# 6_SWITCHING.net
KiCad netlist of a schematic drawn in Altium Designer
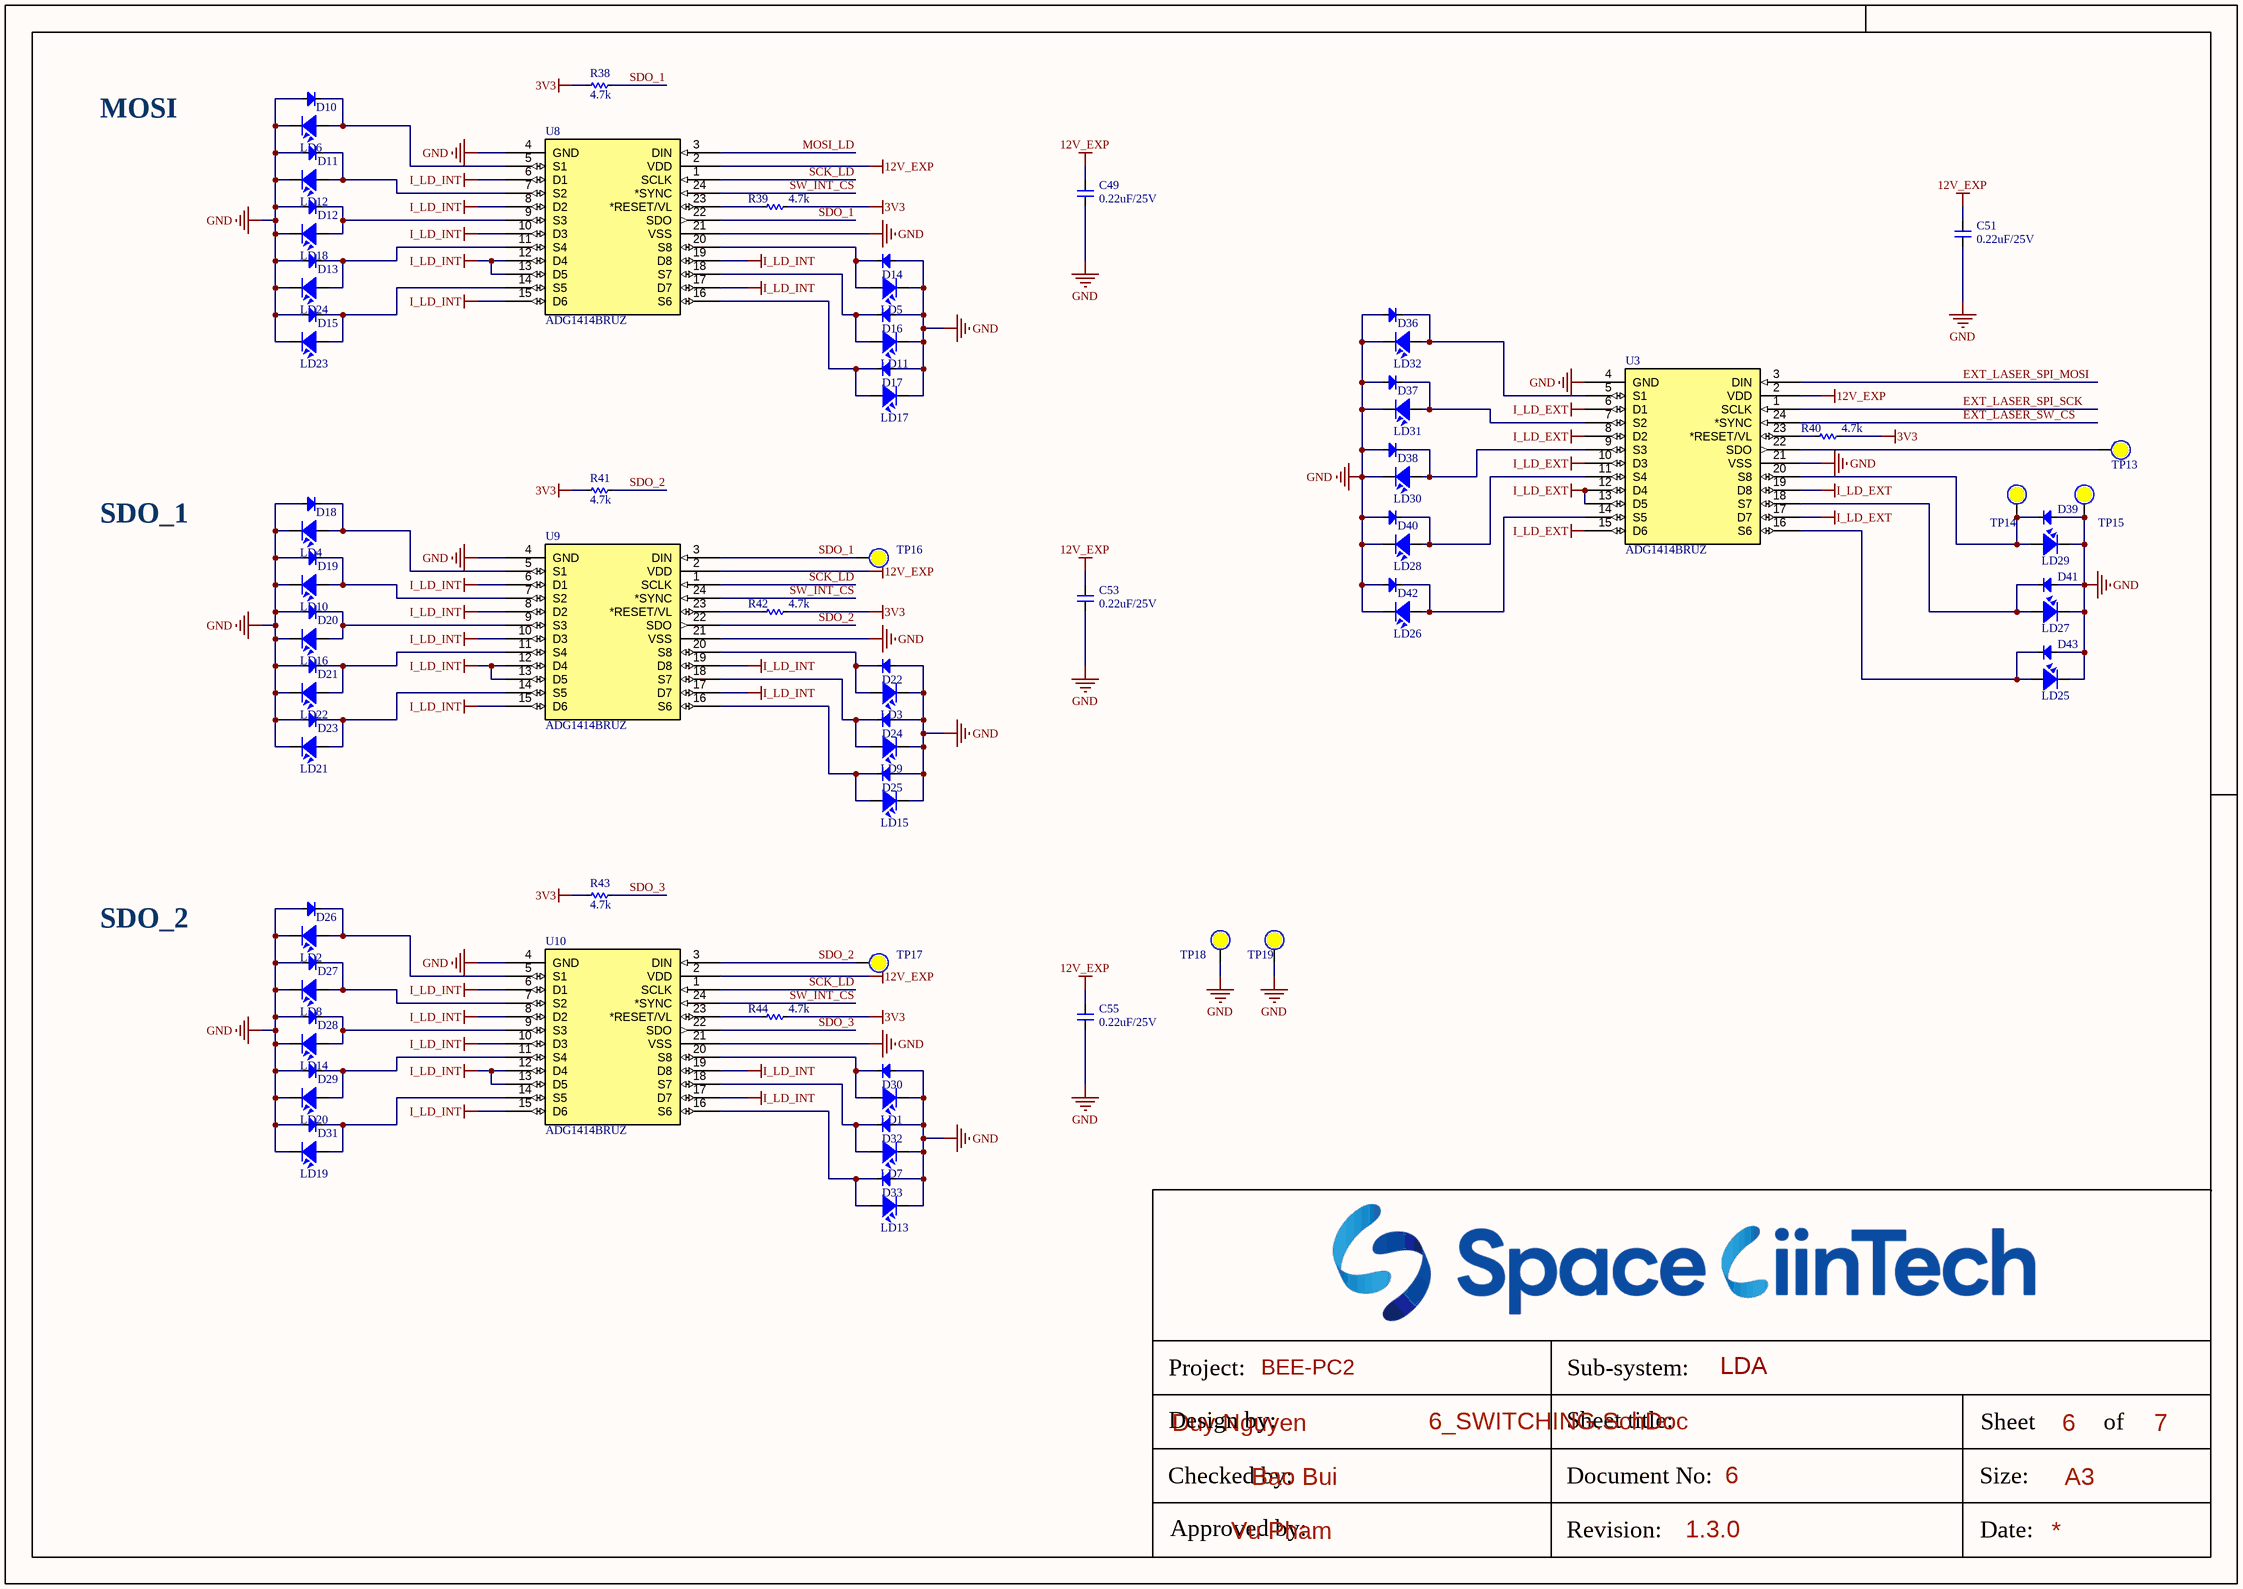
[diagram p0: 6_SWITCHING.SchDoc]

(export (version "E")
  (design (tool "Eeschema 10.0.6"))
  (components
    (comp (ref "C49")
      (value "0.22uF/25V")
      (footprint "CAP_C_1608X80")
      (description "CAP")
      (libsource (lib "LABLIB") (part "_CAP_C_2"))
    )
    (comp (ref "C51")
      (value "0.22uF/25V")
      (footprint "CAP_C_1608X80")
      (description "CAP")
      (libsource (lib "LABLIB") (part "_CAP_C_2"))
    )
    (comp (ref "C53")
      (value "0.22uF/25V")
      (footprint "CAP_C_1608X80")
      (description "CAP")
      (libsource (lib "LABLIB") (part "_CAP_C_2"))
    )
    (comp (ref "C55")
      (value "0.22uF/25V")
      (footprint "CAP_C_1608X80")
      (description "CAP")
      (libsource (lib "LABLIB") (part "_CAP_C_2"))
    )
    (comp (ref "D10")
      (value "1N4148W-TP")
      (footprint "SOD23")
      (fields (field (name "PUBLISHER") "Altium Limited"))
      (libsource (lib "LASER_LIB_SCHE") (part "Diode SMD"))
    )
    (comp (ref "D11")
      (value "1N4148W-TP")
      (footprint "SOD23")
      (fields (field (name "PUBLISHER") "Altium Limited"))
      (libsource (lib "LASER_LIB_SCHE") (part "Diode SMD"))
    )
    (comp (ref "D12")
      (value "1N4148W-TP")
      (footprint "SOD23")
      (fields (field (name "PUBLISHER") "Altium Limited"))
      (libsource (lib "LASER_LIB_SCHE") (part "Diode SMD"))
    )
    (comp (ref "D13")
      (value "1N4148W-TP")
      (footprint "SOD23")
      (fields (field (name "PUBLISHER") "Altium Limited"))
      (libsource (lib "LASER_LIB_SCHE") (part "Diode SMD"))
    )
    (comp (ref "D14")
      (value "1N4148W-TP")
      (footprint "SOD23")
      (fields (field (name "PUBLISHER") "Altium Limited"))
      (libsource (lib "LASER_LIB_SCHE") (part "Diode SMD"))
    )
    (comp (ref "D15")
      (value "1N4148W-TP")
      (footprint "SOD23")
      (fields (field (name "PUBLISHER") "Altium Limited"))
      (libsource (lib "LASER_LIB_SCHE") (part "Diode SMD"))
    )
    (comp (ref "D16")
      (value "1N4148W-TP")
      (footprint "SOD23")
      (fields (field (name "PUBLISHER") "Altium Limited"))
      (libsource (lib "LASER_LIB_SCHE") (part "Diode SMD"))
    )
    (comp (ref "D17")
      (value "1N4148W-TP")
      (footprint "SOD23")
      (fields (field (name "PUBLISHER") "Altium Limited"))
      (libsource (lib "LASER_LIB_SCHE") (part "Diode SMD"))
    )
    (comp (ref "D18")
      (value "1N4148W-TP")
      (footprint "SOD23")
      (fields (field (name "PUBLISHER") "Altium Limited"))
      (libsource (lib "LASER_LIB_SCHE") (part "Diode SMD"))
    )
    (comp (ref "D19")
      (value "1N4148W-TP")
      (footprint "SOD23")
      (fields (field (name "PUBLISHER") "Altium Limited"))
      (libsource (lib "LASER_LIB_SCHE") (part "Diode SMD"))
    )
    (comp (ref "D20")
      (value "1N4148W-TP")
      (footprint "SOD23")
      (fields (field (name "PUBLISHER") "Altium Limited"))
      (libsource (lib "LASER_LIB_SCHE") (part "Diode SMD"))
    )
    (comp (ref "D21")
      (value "1N4148W-TP")
      (footprint "SOD23")
      (fields (field (name "PUBLISHER") "Altium Limited"))
      (libsource (lib "LASER_LIB_SCHE") (part "Diode SMD"))
    )
    (comp (ref "D22")
      (value "1N4148W-TP")
      (footprint "SOD23")
      (fields (field (name "PUBLISHER") "Altium Limited"))
      (libsource (lib "LASER_LIB_SCHE") (part "Diode SMD"))
    )
    (comp (ref "D23")
      (value "1N4148W-TP")
      (footprint "SOD23")
      (fields (field (name "PUBLISHER") "Altium Limited"))
      (libsource (lib "LASER_LIB_SCHE") (part "Diode SMD"))
    )
    (comp (ref "D24")
      (value "1N4148W-TP")
      (footprint "SOD23")
      (fields (field (name "PUBLISHER") "Altium Limited"))
      (libsource (lib "LASER_LIB_SCHE") (part "Diode SMD"))
    )
    (comp (ref "D25")
      (value "1N4148W-TP")
      (footprint "SOD23")
      (fields (field (name "PUBLISHER") "Altium Limited"))
      (libsource (lib "LASER_LIB_SCHE") (part "Diode SMD"))
    )
    (comp (ref "D26")
      (value "1N4148W-TP")
      (footprint "SOD23")
      (fields (field (name "PUBLISHER") "Altium Limited"))
      (libsource (lib "LASER_LIB_SCHE") (part "Diode SMD"))
    )
    (comp (ref "D27")
      (value "1N4148W-TP")
      (footprint "SOD23")
      (fields (field (name "PUBLISHER") "Altium Limited"))
      (libsource (lib "LASER_LIB_SCHE") (part "Diode SMD"))
    )
    (comp (ref "D28")
      (value "1N4148W-TP")
      (footprint "SOD23")
      (fields (field (name "PUBLISHER") "Altium Limited"))
      (libsource (lib "LASER_LIB_SCHE") (part "Diode SMD"))
    )
    (comp (ref "D29")
      (value "1N4148W-TP")
      (footprint "SOD23")
      (fields (field (name "PUBLISHER") "Altium Limited"))
      (libsource (lib "LASER_LIB_SCHE") (part "Diode SMD"))
    )
    (comp (ref "D30")
      (value "1N4148W-TP")
      (footprint "SOD23")
      (fields (field (name "PUBLISHER") "Altium Limited"))
      (libsource (lib "LASER_LIB_SCHE") (part "Diode SMD"))
    )
    (comp (ref "D31")
      (value "1N4148W-TP")
      (footprint "SOD23")
      (fields (field (name "PUBLISHER") "Altium Limited"))
      (libsource (lib "LASER_LIB_SCHE") (part "Diode SMD"))
    )
    (comp (ref "D32")
      (value "1N4148W-TP")
      (footprint "SOD23")
      (fields (field (name "PUBLISHER") "Altium Limited"))
      (libsource (lib "LASER_LIB_SCHE") (part "Diode SMD"))
    )
    (comp (ref "D33")
      (value "1N4148W-TP")
      (footprint "SOD23")
      (fields (field (name "PUBLISHER") "Altium Limited"))
      (libsource (lib "LASER_LIB_SCHE") (part "Diode SMD"))
    )
    (comp (ref "D36")
      (value "1N4148W-TP")
      (footprint "SOD23")
      (fields (field (name "PUBLISHER") "Altium Limited"))
      (libsource (lib "LASER_LIB_SCHE") (part "Diode SMD"))
    )
    (comp (ref "D37")
      (value "1N4148W-TP")
      (footprint "SOD23")
      (fields (field (name "PUBLISHER") "Altium Limited"))
      (libsource (lib "LASER_LIB_SCHE") (part "Diode SMD"))
    )
    (comp (ref "D38")
      (value "1N4148W-TP")
      (footprint "SOD23")
      (fields (field (name "PUBLISHER") "Altium Limited"))
      (libsource (lib "LASER_LIB_SCHE") (part "Diode SMD"))
    )
    (comp (ref "D39")
      (value "1N4148W-TP")
      (footprint "SOD23")
      (fields (field (name "PUBLISHER") "Altium Limited"))
      (libsource (lib "LASER_LIB_SCHE") (part "Diode SMD"))
    )
    (comp (ref "D40")
      (value "1N4148W-TP")
      (footprint "SOD23")
      (fields (field (name "PUBLISHER") "Altium Limited"))
      (libsource (lib "LASER_LIB_SCHE") (part "Diode SMD"))
    )
    (comp (ref "D41")
      (value "1N4148W-TP")
      (footprint "SOD23")
      (fields (field (name "PUBLISHER") "Altium Limited"))
      (libsource (lib "LASER_LIB_SCHE") (part "Diode SMD"))
    )
    (comp (ref "D42")
      (value "1N4148W-TP")
      (footprint "SOD23")
      (fields (field (name "PUBLISHER") "Altium Limited"))
      (libsource (lib "LASER_LIB_SCHE") (part "Diode SMD"))
    )
    (comp (ref "D43")
      (value "1N4148W-TP")
      (footprint "SOD23")
      (fields (field (name "PUBLISHER") "Altium Limited"))
      (libsource (lib "LASER_LIB_SCHE") (part "Diode SMD"))
    )
    (comp (ref "LD1")
      (value "LaserDiode")
      (footprint "OPV302")
      (description "OPV302")
      (libsource (lib "LASER_LIB_SCHE") (part "LD"))
    )
    (comp (ref "LD2")
      (value "LaserDiode")
      (footprint "OPV302")
      (description "OPV302")
      (libsource (lib "LASER_LIB_SCHE") (part "LD"))
    )
    (comp (ref "LD3")
      (value "LaserDiode")
      (footprint "OPV302")
      (description "OPV302")
      (libsource (lib "LASER_LIB_SCHE") (part "LD"))
    )
    (comp (ref "LD4")
      (value "LaserDiode")
      (footprint "OPV302")
      (description "OPV302")
      (libsource (lib "LASER_LIB_SCHE") (part "LD"))
    )
    (comp (ref "LD5")
      (value "LaserDiode")
      (footprint "OPV302")
      (description "OPV302")
      (libsource (lib "LASER_LIB_SCHE") (part "LD"))
    )
    (comp (ref "LD6")
      (value "LaserDiode")
      (footprint "OPV302")
      (description "OPV302")
      (libsource (lib "LASER_LIB_SCHE") (part "LD"))
    )
    (comp (ref "LD7")
      (value "LaserDiode")
      (footprint "OPV302")
      (description "OPV302")
      (libsource (lib "LASER_LIB_SCHE") (part "LD"))
    )
    (comp (ref "LD8")
      (value "LaserDiode")
      (footprint "OPV302")
      (description "OPV302")
      (libsource (lib "LASER_LIB_SCHE") (part "LD"))
    )
    (comp (ref "LD9")
      (value "LaserDiode")
      (footprint "OPV302")
      (description "OPV302")
      (libsource (lib "LASER_LIB_SCHE") (part "LD"))
    )
    (comp (ref "LD10")
      (value "LaserDiode")
      (footprint "OPV302")
      (description "OPV302")
      (libsource (lib "LASER_LIB_SCHE") (part "LD"))
    )
    (comp (ref "LD11")
      (value "LaserDiode")
      (footprint "OPV302")
      (description "OPV302")
      (libsource (lib "LASER_LIB_SCHE") (part "LD"))
    )
    (comp (ref "LD12")
      (value "LaserDiode")
      (footprint "OPV302")
      (description "OPV302")
      (libsource (lib "LASER_LIB_SCHE") (part "LD"))
    )
    (comp (ref "LD13")
      (value "LaserDiode")
      (footprint "OPV302")
      (description "OPV302")
      (libsource (lib "LASER_LIB_SCHE") (part "LD"))
    )
    (comp (ref "LD14")
      (value "LaserDiode")
      (footprint "OPV302")
      (description "OPV302")
      (libsource (lib "LASER_LIB_SCHE") (part "LD"))
    )
    (comp (ref "LD15")
      (value "LaserDiode")
      (footprint "OPV302")
      (description "OPV302")
      (libsource (lib "LASER_LIB_SCHE") (part "LD"))
    )
    (comp (ref "LD16")
      (value "LaserDiode")
      (footprint "OPV302")
      (description "OPV302")
      (libsource (lib "LASER_LIB_SCHE") (part "LD"))
    )
    (comp (ref "LD17")
      (value "LaserDiode")
      (footprint "OPV302")
      (description "OPV302")
      (libsource (lib "LASER_LIB_SCHE") (part "LD"))
    )
    (comp (ref "LD18")
      (value "LaserDiode")
      (footprint "OPV302")
      (description "OPV302")
      (libsource (lib "LASER_LIB_SCHE") (part "LD"))
    )
    (comp (ref "LD19")
      (value "LaserDiode")
      (footprint "OPV302")
      (description "OPV302")
      (libsource (lib "LASER_LIB_SCHE") (part "LD"))
    )
    (comp (ref "LD20")
      (value "LaserDiode")
      (footprint "OPV302")
      (description "OPV302")
      (libsource (lib "LASER_LIB_SCHE") (part "LD"))
    )
    (comp (ref "LD21")
      (value "LaserDiode")
      (footprint "OPV302")
      (description "OPV302")
      (libsource (lib "LASER_LIB_SCHE") (part "LD"))
    )
    (comp (ref "LD22")
      (value "LaserDiode")
      (footprint "OPV302")
      (description "OPV302")
      (libsource (lib "LASER_LIB_SCHE") (part "LD"))
    )
    (comp (ref "LD23")
      (value "LaserDiode")
      (footprint "OPV302")
      (description "OPV302")
      (libsource (lib "LASER_LIB_SCHE") (part "LD"))
    )
    (comp (ref "LD24")
      (value "LaserDiode")
      (footprint "OPV302")
      (description "OPV302")
      (libsource (lib "LASER_LIB_SCHE") (part "LD"))
    )
    (comp (ref "LD25")
      (value "LaserDiode")
      (footprint "RLD65NZX1")
      (description "RLD65NZX1")
      (libsource (lib "LASER_LIB_SCHE") (part "LD_RLD65NZX1"))
    )
    (comp (ref "LD26")
      (value "LaserDiode")
      (footprint "RLD65NZX1")
      (description "RLD65NZX1")
      (libsource (lib "LASER_LIB_SCHE") (part "LD_RLD65NZX1"))
    )
    (comp (ref "LD27")
      (value "LaserDiode")
      (footprint "RLD65NZX1")
      (description "RLD65NZX1")
      (libsource (lib "LASER_LIB_SCHE") (part "LD_RLD65NZX1"))
    )
    (comp (ref "LD28")
      (value "LaserDiode")
      (footprint "RLD65NZX1")
      (description "RLD65NZX1")
      (libsource (lib "LASER_LIB_SCHE") (part "LD_RLD65NZX1"))
    )
    (comp (ref "LD29")
      (value "LaserDiode")
      (footprint "RLD65NZX1")
      (description "RLD65NZX1")
      (libsource (lib "LASER_LIB_SCHE") (part "LD_RLD65NZX1"))
    )
    (comp (ref "LD30")
      (value "LaserDiode")
      (footprint "RLD65NZX1")
      (description "RLD65NZX1")
      (libsource (lib "LASER_LIB_SCHE") (part "LD_RLD65NZX1"))
    )
    (comp (ref "LD31")
      (value "LaserDiode")
      (footprint "RLD65NZX1")
      (description "RLD65NZX1")
      (libsource (lib "LASER_LIB_SCHE") (part "LD_RLD65NZX1"))
    )
    (comp (ref "LD32")
      (value "LaserDiode")
      (footprint "RLD65NZX1")
      (description "RLD65NZX1")
      (libsource (lib "LASER_LIB_SCHE") (part "LD_RLD65NZX1"))
    )
    (comp (ref "R38")
      (value "4.7k")
      (footprint "RES_C_1608X60")
      (description "RES")
      (libsource (lib "LABLIB") (part "_RES_B_2"))
    )
    (comp (ref "R39")
      (value "4.7k")
      (footprint "RES_C_1608X60")
      (description "RES")
      (libsource (lib "LABLIB") (part "_RES_B_2"))
    )
    (comp (ref "R40")
      (value "4.7k")
      (footprint "RES_C_1608X60")
      (description "RES")
      (libsource (lib "LABLIB") (part "_RES_B_2"))
    )
    (comp (ref "R41")
      (value "4.7k")
      (footprint "RES_C_1608X60")
      (description "RES")
      (libsource (lib "LABLIB") (part "_RES_B_2"))
    )
    (comp (ref "R42")
      (value "4.7k")
      (footprint "RES_C_1608X60")
      (description "RES")
      (libsource (lib "LABLIB") (part "_RES_B_2"))
    )
    (comp (ref "R43")
      (value "4.7k")
      (footprint "RES_C_1608X60")
      (description "RES")
      (libsource (lib "LABLIB") (part "_RES_B_2"))
    )
    (comp (ref "R44")
      (value "4.7k")
      (footprint "RES_C_1608X60")
      (description "RES")
      (libsource (lib "LABLIB") (part "_RES_B_2"))
    )
    (comp (ref "TP13")
      (value "~")
      (footprint "Testpoint_80")
      (description "Test Point")
      (libsource (lib "LASER_LIB_SCHE") (part "Test Point"))
    )
    (comp (ref "TP14")
      (value "~")
      (footprint "Testpoint_80")
      (description "Test Point")
      (libsource (lib "") (part "Test Point_1"))
    )
    (comp (ref "TP15")
      (value "~")
      (footprint "Testpoint_80")
      (description "Test Point")
      (libsource (lib "") (part "Test Point_1"))
    )
    (comp (ref "TP16")
      (value "~")
      (footprint "Testpoint_80")
      (description "Test Point")
      (libsource (lib "LASER_LIB_SCHE") (part "Test Point"))
    )
    (comp (ref "TP17")
      (value "~")
      (footprint "Testpoint_80")
      (description "Test Point")
      (libsource (lib "LASER_LIB_SCHE") (part "Test Point"))
    )
    (comp (ref "TP18")
      (value "~")
      (footprint "Testpoint_80")
      (description "Test Point")
      (libsource (lib "") (part "Test Point_1"))
    )
    (comp (ref "TP19")
      (value "~")
      (footprint "Testpoint_80")
      (description "Test Point")
      (libsource (lib "") (part "Test Point_1"))
    )
    (comp (ref "U3")
      (value "ADG1414BRUZ")
      (footprint "TSSOP24")
      (libsource (lib "LASER_LIB_SCHE") (part "ADG1414BRUZ"))
    )
    (comp (ref "U8")
      (value "ADG1414BRUZ")
      (footprint "TSSOP24")
      (libsource (lib "LASER_LIB_SCHE") (part "ADG1414BRUZ"))
    )
    (comp (ref "U9")
      (value "ADG1414BRUZ")
      (footprint "TSSOP24")
      (libsource (lib "LASER_LIB_SCHE") (part "ADG1414BRUZ"))
    )
    (comp (ref "U10")
      (value "ADG1414BRUZ")
      (footprint "TSSOP24")
      (libsource (lib "LASER_LIB_SCHE") (part "ADG1414BRUZ"))
    )
  )
  (nets
    (net (code "1") (name "/EXT_LASER_SPI_MOSI") (class "Default")
      (node (ref "U3") (pin "3") (pinfunction "DIN_3") (pintype "input"))
    )
    (net (code "2") (name "/EXT_LASER_SPI_SCK") (class "Default")
      (node (ref "U3") (pin "1") (pinfunction "SCLK_1") (pintype "input"))
    )
    (net (code "3") (name "/EXT_LASER_SW_CS") (class "Default")
      (node (ref "U3") (pin "24") (pinfunction "*SYNC_24") (pintype "input"))
    )
    (net (code "4") (name "/MOSI_LD") (class "Default")
      (node (ref "U8") (pin "3") (pinfunction "DIN_3") (pintype "input"))
    )
    (net (code "5") (name "/SCK_LD") (class "Default")
      (node (ref "U10") (pin "1") (pinfunction "SCLK_1") (pintype "input"))
      (node (ref "U8") (pin "1") (pinfunction "SCLK_1") (pintype "input"))
      (node (ref "U9") (pin "1") (pinfunction "SCLK_1") (pintype "input"))
    )
    (net (code "6") (name "/SDO_1") (class "Default")
      (node (ref "R38") (pin "2") (pinfunction "2_2") (pintype "passive"))
      (node (ref "TP16") (pin "1") (pinfunction "1_1") (pintype "passive"))
      (node (ref "U8") (pin "22") (pinfunction "SDO_22") (pintype "output"))
      (node (ref "U9") (pin "3") (pinfunction "DIN_3") (pintype "input"))
    )
    (net (code "7") (name "/SDO_2") (class "Default")
      (node (ref "R41") (pin "2") (pinfunction "2_2") (pintype "passive"))
      (node (ref "TP17") (pin "1") (pinfunction "1_1") (pintype "passive"))
      (node (ref "U10") (pin "3") (pinfunction "DIN_3") (pintype "input"))
      (node (ref "U9") (pin "22") (pinfunction "SDO_22") (pintype "output"))
    )
    (net (code "8") (name "/SDO_3") (class "Default")
      (node (ref "R43") (pin "2") (pinfunction "2_2") (pintype "passive"))
      (node (ref "U10") (pin "22") (pinfunction "SDO_22") (pintype "output"))
    )
    (net (code "9") (name "/SW_INT_CS") (class "Default")
      (node (ref "U10") (pin "24") (pinfunction "*SYNC_24") (pintype "input"))
      (node (ref "U8") (pin "24") (pinfunction "*SYNC_24") (pintype "input"))
      (node (ref "U9") (pin "24") (pinfunction "*SYNC_24") (pintype "input"))
    )
    (net (code "10") (name "3V3") (class "Default")
      (node (ref "R38") (pin "1") (pinfunction "1_1") (pintype "passive"))
      (node (ref "R39") (pin "2") (pinfunction "2_2") (pintype "passive"))
      (node (ref "R40") (pin "2") (pinfunction "2_2") (pintype "passive"))
      (node (ref "R41") (pin "1") (pinfunction "1_1") (pintype "passive"))
      (node (ref "R42") (pin "2") (pinfunction "2_2") (pintype "passive"))
      (node (ref "R43") (pin "1") (pinfunction "1_1") (pintype "passive"))
      (node (ref "R44") (pin "2") (pinfunction "2_2") (pintype "passive"))
    )
    (net (code "11") (name "12V_EXP") (class "Default")
      (node (ref "C49") (pin "2") (pinfunction "2_2") (pintype "passive"))
      (node (ref "C51") (pin "2") (pinfunction "2_2") (pintype "passive"))
      (node (ref "C53") (pin "2") (pinfunction "2_2") (pintype "passive"))
      (node (ref "C55") (pin "2") (pinfunction "2_2") (pintype "passive"))
      (node (ref "U10") (pin "2") (pinfunction "VDD_2") (pintype "power_in"))
      (node (ref "U3") (pin "2") (pinfunction "VDD_2") (pintype "power_in"))
      (node (ref "U8") (pin "2") (pinfunction "VDD_2") (pintype "power_in"))
      (node (ref "U9") (pin "2") (pinfunction "VDD_2") (pintype "power_in"))
    )
    (net (code "12") (name "GND") (class "Default")
      (node (ref "C49") (pin "1") (pinfunction "1_1") (pintype "passive"))
      (node (ref "C51") (pin "1") (pinfunction "1_1") (pintype "passive"))
      (node (ref "C53") (pin "1") (pinfunction "1_1") (pintype "passive"))
      (node (ref "C55") (pin "1") (pinfunction "1_1") (pintype "passive"))
      (node (ref "D10") (pin "1") (pinfunction "A_1") (pintype "passive"))
      (node (ref "D11") (pin "1") (pinfunction "A_1") (pintype "passive"))
      (node (ref "D12") (pin "1") (pinfunction "A_1") (pintype "passive"))
      (node (ref "D13") (pin "1") (pinfunction "A_1") (pintype "passive"))
      (node (ref "D14") (pin "1") (pinfunction "A_1") (pintype "passive"))
      (node (ref "D15") (pin "1") (pinfunction "A_1") (pintype "passive"))
      (node (ref "D16") (pin "1") (pinfunction "A_1") (pintype "passive"))
      (node (ref "D17") (pin "1") (pinfunction "A_1") (pintype "passive"))
      (node (ref "D18") (pin "1") (pinfunction "A_1") (pintype "passive"))
      (node (ref "D19") (pin "1") (pinfunction "A_1") (pintype "passive"))
      (node (ref "D20") (pin "1") (pinfunction "A_1") (pintype "passive"))
      (node (ref "D21") (pin "1") (pinfunction "A_1") (pintype "passive"))
      (node (ref "D22") (pin "1") (pinfunction "A_1") (pintype "passive"))
      (node (ref "D23") (pin "1") (pinfunction "A_1") (pintype "passive"))
      (node (ref "D24") (pin "1") (pinfunction "A_1") (pintype "passive"))
      (node (ref "D25") (pin "1") (pinfunction "A_1") (pintype "passive"))
      (node (ref "D26") (pin "1") (pinfunction "A_1") (pintype "passive"))
      (node (ref "D27") (pin "1") (pinfunction "A_1") (pintype "passive"))
      (node (ref "D28") (pin "1") (pinfunction "A_1") (pintype "passive"))
      (node (ref "D29") (pin "1") (pinfunction "A_1") (pintype "passive"))
      (node (ref "D30") (pin "1") (pinfunction "A_1") (pintype "passive"))
      (node (ref "D31") (pin "1") (pinfunction "A_1") (pintype "passive"))
      (node (ref "D32") (pin "1") (pinfunction "A_1") (pintype "passive"))
      (node (ref "D33") (pin "1") (pinfunction "A_1") (pintype "passive"))
      (node (ref "D36") (pin "1") (pinfunction "A_1") (pintype "passive"))
      (node (ref "D37") (pin "1") (pinfunction "A_1") (pintype "passive"))
      (node (ref "D38") (pin "1") (pinfunction "A_1") (pintype "passive"))
      (node (ref "D39") (pin "1") (pinfunction "A_1") (pintype "passive"))
      (node (ref "D40") (pin "1") (pinfunction "A_1") (pintype "passive"))
      (node (ref "D41") (pin "1") (pinfunction "A_1") (pintype "passive"))
      (node (ref "D42") (pin "1") (pinfunction "A_1") (pintype "passive"))
      (node (ref "D43") (pin "1") (pinfunction "A_1") (pintype "passive"))
      (node (ref "LD1") (pin "2") (pinfunction "2_2") (pintype "passive"))
      (node (ref "LD10") (pin "2") (pinfunction "2_2") (pintype "passive"))
      (node (ref "LD11") (pin "2") (pinfunction "2_2") (pintype "passive"))
      (node (ref "LD12") (pin "2") (pinfunction "2_2") (pintype "passive"))
      (node (ref "LD13") (pin "2") (pinfunction "2_2") (pintype "passive"))
      (node (ref "LD14") (pin "2") (pinfunction "2_2") (pintype "passive"))
      (node (ref "LD15") (pin "2") (pinfunction "2_2") (pintype "passive"))
      (node (ref "LD16") (pin "2") (pinfunction "2_2") (pintype "passive"))
      (node (ref "LD17") (pin "2") (pinfunction "2_2") (pintype "passive"))
      (node (ref "LD18") (pin "2") (pinfunction "2_2") (pintype "passive"))
      (node (ref "LD19") (pin "2") (pinfunction "2_2") (pintype "passive"))
      (node (ref "LD2") (pin "2") (pinfunction "2_2") (pintype "passive"))
      (node (ref "LD20") (pin "2") (pinfunction "2_2") (pintype "passive"))
      (node (ref "LD21") (pin "2") (pinfunction "2_2") (pintype "passive"))
      (node (ref "LD22") (pin "2") (pinfunction "2_2") (pintype "passive"))
      (node (ref "LD23") (pin "2") (pinfunction "2_2") (pintype "passive"))
      (node (ref "LD24") (pin "2") (pinfunction "2_2") (pintype "passive"))
      (node (ref "LD25") (pin "1") (pinfunction "1_1") (pintype "passive"))
      (node (ref "LD26") (pin "1") (pinfunction "1_1") (pintype "passive"))
      (node (ref "LD27") (pin "1") (pinfunction "1_1") (pintype "passive"))
      (node (ref "LD28") (pin "1") (pinfunction "1_1") (pintype "passive"))
      (node (ref "LD29") (pin "1") (pinfunction "1_1") (pintype "passive"))
      (node (ref "LD3") (pin "2") (pinfunction "2_2") (pintype "passive"))
      (node (ref "LD30") (pin "1") (pinfunction "1_1") (pintype "passive"))
      (node (ref "LD31") (pin "1") (pinfunction "1_1") (pintype "passive"))
      (node (ref "LD32") (pin "1") (pinfunction "1_1") (pintype "passive"))
      (node (ref "LD4") (pin "2") (pinfunction "2_2") (pintype "passive"))
      (node (ref "LD5") (pin "2") (pinfunction "2_2") (pintype "passive"))
      (node (ref "LD6") (pin "2") (pinfunction "2_2") (pintype "passive"))
      (node (ref "LD7") (pin "2") (pinfunction "2_2") (pintype "passive"))
      (node (ref "LD8") (pin "2") (pinfunction "2_2") (pintype "passive"))
      (node (ref "LD9") (pin "2") (pinfunction "2_2") (pintype "passive"))
      (node (ref "TP15") (pin "1") (pinfunction "1_1") (pintype "passive"))
      (node (ref "TP18") (pin "1") (pinfunction "1_1") (pintype "passive"))
      (node (ref "TP19") (pin "1") (pinfunction "1_1") (pintype "passive"))
      (node (ref "U10") (pin "21") (pinfunction "VSS_21") (pintype "power_in"))
      (node (ref "U10") (pin "4") (pinfunction "GND_4") (pintype "power_in"))
      (node (ref "U3") (pin "21") (pinfunction "VSS_21") (pintype "power_in"))
      (node (ref "U3") (pin "4") (pinfunction "GND_4") (pintype "power_in"))
      (node (ref "U8") (pin "21") (pinfunction "VSS_21") (pintype "power_in"))
      (node (ref "U8") (pin "4") (pinfunction "GND_4") (pintype "power_in"))
      (node (ref "U9") (pin "21") (pinfunction "VSS_21") (pintype "power_in"))
      (node (ref "U9") (pin "4") (pinfunction "GND_4") (pintype "power_in"))
    )
    (net (code "13") (name "I_LD_EXT") (class "Default")
      (node (ref "U3") (pin "10") (pinfunction "D3_10") (pintype "bidirectional"))
      (node (ref "U3") (pin "12") (pinfunction "D4_12") (pintype "bidirectional"))
      (node (ref "U3") (pin "13") (pinfunction "D5_13") (pintype "bidirectional"))
      (node (ref "U3") (pin "15") (pinfunction "D6_15") (pintype "bidirectional"))
      (node (ref "U3") (pin "17") (pinfunction "D7_17") (pintype "bidirectional"))
      (node (ref "U3") (pin "19") (pinfunction "D8_19") (pintype "bidirectional"))
      (node (ref "U3") (pin "6") (pinfunction "D1_6") (pintype "bidirectional"))
      (node (ref "U3") (pin "8") (pinfunction "D2_8") (pintype "bidirectional"))
    )
    (net (code "14") (name "I_LD_INT") (class "Default")
      (node (ref "U10") (pin "10") (pinfunction "D3_10") (pintype "bidirectional"))
      (node (ref "U10") (pin "12") (pinfunction "D4_12") (pintype "bidirectional"))
      (node (ref "U10") (pin "13") (pinfunction "D5_13") (pintype "bidirectional"))
      (node (ref "U10") (pin "15") (pinfunction "D6_15") (pintype "bidirectional"))
      (node (ref "U10") (pin "17") (pinfunction "D7_17") (pintype "bidirectional"))
      (node (ref "U10") (pin "19") (pinfunction "D8_19") (pintype "bidirectional"))
      (node (ref "U10") (pin "6") (pinfunction "D1_6") (pintype "bidirectional"))
      (node (ref "U10") (pin "8") (pinfunction "D2_8") (pintype "bidirectional"))
      (node (ref "U8") (pin "10") (pinfunction "D3_10") (pintype "bidirectional"))
      (node (ref "U8") (pin "12") (pinfunction "D4_12") (pintype "bidirectional"))
      (node (ref "U8") (pin "13") (pinfunction "D5_13") (pintype "bidirectional"))
      (node (ref "U8") (pin "15") (pinfunction "D6_15") (pintype "bidirectional"))
      (node (ref "U8") (pin "17") (pinfunction "D7_17") (pintype "bidirectional"))
      (node (ref "U8") (pin "19") (pinfunction "D8_19") (pintype "bidirectional"))
      (node (ref "U8") (pin "6") (pinfunction "D1_6") (pintype "bidirectional"))
      (node (ref "U8") (pin "8") (pinfunction "D2_8") (pintype "bidirectional"))
      (node (ref "U9") (pin "10") (pinfunction "D3_10") (pintype "bidirectional"))
      (node (ref "U9") (pin "12") (pinfunction "D4_12") (pintype "bidirectional"))
      (node (ref "U9") (pin "13") (pinfunction "D5_13") (pintype "bidirectional"))
      (node (ref "U9") (pin "15") (pinfunction "D6_15") (pintype "bidirectional"))
      (node (ref "U9") (pin "17") (pinfunction "D7_17") (pintype "bidirectional"))
      (node (ref "U9") (pin "19") (pinfunction "D8_19") (pintype "bidirectional"))
      (node (ref "U9") (pin "6") (pinfunction "D1_6") (pintype "bidirectional"))
      (node (ref "U9") (pin "8") (pinfunction "D2_8") (pintype "bidirectional"))
    )
    (net (code "15") (name "Net-(D10-K)") (class "Default")
      (node (ref "D10") (pin "2") (pinfunction "K_2") (pintype "passive"))
      (node (ref "LD6") (pin "1") (pinfunction "1_1") (pintype "passive"))
      (node (ref "U8") (pin "5") (pinfunction "S1_5") (pintype "bidirectional"))
    )
    (net (code "16") (name "Net-(D11-K)") (class "Default")
      (node (ref "D11") (pin "2") (pinfunction "K_2") (pintype "passive"))
      (node (ref "LD12") (pin "1") (pinfunction "1_1") (pintype "passive"))
      (node (ref "U8") (pin "7") (pinfunction "S2_7") (pintype "bidirectional"))
    )
    (net (code "17") (name "Net-(D12-K)") (class "Default")
      (node (ref "D12") (pin "2") (pinfunction "K_2") (pintype "passive"))
      (node (ref "LD18") (pin "1") (pinfunction "1_1") (pintype "passive"))
      (node (ref "U8") (pin "9") (pinfunction "S3_9") (pintype "bidirectional"))
    )
    (net (code "18") (name "Net-(D13-K)") (class "Default")
      (node (ref "D13") (pin "2") (pinfunction "K_2") (pintype "passive"))
      (node (ref "LD24") (pin "1") (pinfunction "1_1") (pintype "passive"))
      (node (ref "U8") (pin "11") (pinfunction "S4_11") (pintype "bidirectional"))
    )
    (net (code "19") (name "Net-(D14-K)") (class "Default")
      (node (ref "D14") (pin "2") (pinfunction "K_2") (pintype "passive"))
      (node (ref "LD5") (pin "1") (pinfunction "1_1") (pintype "passive"))
      (node (ref "U8") (pin "20") (pinfunction "S8_20") (pintype "bidirectional"))
    )
    (net (code "20") (name "Net-(D15-K)") (class "Default")
      (node (ref "D15") (pin "2") (pinfunction "K_2") (pintype "passive"))
      (node (ref "LD23") (pin "1") (pinfunction "1_1") (pintype "passive"))
      (node (ref "U8") (pin "14") (pinfunction "S5_14") (pintype "bidirectional"))
    )
    (net (code "21") (name "Net-(D16-K)") (class "Default")
      (node (ref "D16") (pin "2") (pinfunction "K_2") (pintype "passive"))
      (node (ref "LD11") (pin "1") (pinfunction "1_1") (pintype "passive"))
      (node (ref "U8") (pin "18") (pinfunction "S7_18") (pintype "bidirectional"))
    )
    (net (code "22") (name "Net-(D17-K)") (class "Default")
      (node (ref "D17") (pin "2") (pinfunction "K_2") (pintype "passive"))
      (node (ref "LD17") (pin "1") (pinfunction "1_1") (pintype "passive"))
      (node (ref "U8") (pin "16") (pinfunction "S6_16") (pintype "bidirectional"))
    )
    (net (code "23") (name "Net-(D18-K)") (class "Default")
      (node (ref "D18") (pin "2") (pinfunction "K_2") (pintype "passive"))
      (node (ref "LD4") (pin "1") (pinfunction "1_1") (pintype "passive"))
      (node (ref "U9") (pin "5") (pinfunction "S1_5") (pintype "bidirectional"))
    )
    (net (code "24") (name "Net-(D19-K)") (class "Default")
      (node (ref "D19") (pin "2") (pinfunction "K_2") (pintype "passive"))
      (node (ref "LD10") (pin "1") (pinfunction "1_1") (pintype "passive"))
      (node (ref "U9") (pin "7") (pinfunction "S2_7") (pintype "bidirectional"))
    )
    (net (code "25") (name "Net-(D20-K)") (class "Default")
      (node (ref "D20") (pin "2") (pinfunction "K_2") (pintype "passive"))
      (node (ref "LD16") (pin "1") (pinfunction "1_1") (pintype "passive"))
      (node (ref "U9") (pin "9") (pinfunction "S3_9") (pintype "bidirectional"))
    )
    (net (code "26") (name "Net-(D21-K)") (class "Default")
      (node (ref "D21") (pin "2") (pinfunction "K_2") (pintype "passive"))
      (node (ref "LD22") (pin "1") (pinfunction "1_1") (pintype "passive"))
      (node (ref "U9") (pin "11") (pinfunction "S4_11") (pintype "bidirectional"))
    )
    (net (code "27") (name "Net-(D22-K)") (class "Default")
      (node (ref "D22") (pin "2") (pinfunction "K_2") (pintype "passive"))
      (node (ref "LD3") (pin "1") (pinfunction "1_1") (pintype "passive"))
      (node (ref "U9") (pin "20") (pinfunction "S8_20") (pintype "bidirectional"))
    )
    (net (code "28") (name "Net-(D23-K)") (class "Default")
      (node (ref "D23") (pin "2") (pinfunction "K_2") (pintype "passive"))
      (node (ref "LD21") (pin "1") (pinfunction "1_1") (pintype "passive"))
      (node (ref "U9") (pin "14") (pinfunction "S5_14") (pintype "bidirectional"))
    )
    (net (code "29") (name "Net-(D24-K)") (class "Default")
      (node (ref "D24") (pin "2") (pinfunction "K_2") (pintype "passive"))
      (node (ref "LD9") (pin "1") (pinfunction "1_1") (pintype "passive"))
      (node (ref "U9") (pin "18") (pinfunction "S7_18") (pintype "bidirectional"))
    )
    (net (code "30") (name "Net-(D25-K)") (class "Default")
      (node (ref "D25") (pin "2") (pinfunction "K_2") (pintype "passive"))
      (node (ref "LD15") (pin "1") (pinfunction "1_1") (pintype "passive"))
      (node (ref "U9") (pin "16") (pinfunction "S6_16") (pintype "bidirectional"))
    )
    (net (code "31") (name "Net-(D26-K)") (class "Default")
      (node (ref "D26") (pin "2") (pinfunction "K_2") (pintype "passive"))
      (node (ref "LD2") (pin "1") (pinfunction "1_1") (pintype "passive"))
      (node (ref "U10") (pin "5") (pinfunction "S1_5") (pintype "bidirectional"))
    )
    (net (code "32") (name "Net-(D27-K)") (class "Default")
      (node (ref "D27") (pin "2") (pinfunction "K_2") (pintype "passive"))
      (node (ref "LD8") (pin "1") (pinfunction "1_1") (pintype "passive"))
      (node (ref "U10") (pin "7") (pinfunction "S2_7") (pintype "bidirectional"))
    )
    (net (code "33") (name "Net-(D28-K)") (class "Default")
      (node (ref "D28") (pin "2") (pinfunction "K_2") (pintype "passive"))
      (node (ref "LD14") (pin "1") (pinfunction "1_1") (pintype "passive"))
      (node (ref "U10") (pin "9") (pinfunction "S3_9") (pintype "bidirectional"))
    )
    (net (code "34") (name "Net-(D29-K)") (class "Default")
      (node (ref "D29") (pin "2") (pinfunction "K_2") (pintype "passive"))
      (node (ref "LD20") (pin "1") (pinfunction "1_1") (pintype "passive"))
      (node (ref "U10") (pin "11") (pinfunction "S4_11") (pintype "bidirectional"))
    )
    (net (code "35") (name "Net-(D30-K)") (class "Default")
      (node (ref "D30") (pin "2") (pinfunction "K_2") (pintype "passive"))
      (node (ref "LD1") (pin "1") (pinfunction "1_1") (pintype "passive"))
      (node (ref "U10") (pin "20") (pinfunction "S8_20") (pintype "bidirectional"))
    )
    (net (code "36") (name "Net-(D31-K)") (class "Default")
      (node (ref "D31") (pin "2") (pinfunction "K_2") (pintype "passive"))
      (node (ref "LD19") (pin "1") (pinfunction "1_1") (pintype "passive"))
      (node (ref "U10") (pin "14") (pinfunction "S5_14") (pintype "bidirectional"))
    )
    (net (code "37") (name "Net-(D32-K)") (class "Default")
      (node (ref "D32") (pin "2") (pinfunction "K_2") (pintype "passive"))
      (node (ref "LD7") (pin "1") (pinfunction "1_1") (pintype "passive"))
      (node (ref "U10") (pin "18") (pinfunction "S7_18") (pintype "bidirectional"))
    )
    (net (code "38") (name "Net-(D33-K)") (class "Default")
      (node (ref "D33") (pin "2") (pinfunction "K_2") (pintype "passive"))
      (node (ref "LD13") (pin "1") (pinfunction "1_1") (pintype "passive"))
      (node (ref "U10") (pin "16") (pinfunction "S6_16") (pintype "bidirectional"))
    )
    (net (code "39") (name "Net-(D36-K)") (class "Default")
      (node (ref "D36") (pin "2") (pinfunction "K_2") (pintype "passive"))
      (node (ref "LD32") (pin "3") (pinfunction "3_3") (pintype "passive"))
      (node (ref "U3") (pin "5") (pinfunction "S1_5") (pintype "bidirectional"))
    )
    (net (code "40") (name "Net-(D37-K)") (class "Default")
      (node (ref "D37") (pin "2") (pinfunction "K_2") (pintype "passive"))
      (node (ref "LD31") (pin "3") (pinfunction "3_3") (pintype "passive"))
      (node (ref "U3") (pin "7") (pinfunction "S2_7") (pintype "bidirectional"))
    )
    (net (code "41") (name "Net-(D38-K)") (class "Default")
      (node (ref "D38") (pin "2") (pinfunction "K_2") (pintype "passive"))
      (node (ref "LD30") (pin "3") (pinfunction "3_3") (pintype "passive"))
      (node (ref "U3") (pin "9") (pinfunction "S3_9") (pintype "bidirectional"))
    )
    (net (code "42") (name "Net-(D39-K)") (class "Default")
      (node (ref "D39") (pin "2") (pinfunction "K_2") (pintype "passive"))
      (node (ref "LD29") (pin "3") (pinfunction "3_3") (pintype "passive"))
      (node (ref "TP14") (pin "1") (pinfunction "1_1") (pintype "passive"))
      (node (ref "U3") (pin "20") (pinfunction "S8_20") (pintype "bidirectional"))
    )
    (net (code "43") (name "Net-(D40-K)") (class "Default")
      (node (ref "D40") (pin "2") (pinfunction "K_2") (pintype "passive"))
      (node (ref "LD28") (pin "3") (pinfunction "3_3") (pintype "passive"))
      (node (ref "U3") (pin "11") (pinfunction "S4_11") (pintype "bidirectional"))
    )
    (net (code "44") (name "Net-(D41-K)") (class "Default")
      (node (ref "D41") (pin "2") (pinfunction "K_2") (pintype "passive"))
      (node (ref "LD27") (pin "3") (pinfunction "3_3") (pintype "passive"))
      (node (ref "U3") (pin "18") (pinfunction "S7_18") (pintype "bidirectional"))
    )
    (net (code "45") (name "Net-(D42-K)") (class "Default")
      (node (ref "D42") (pin "2") (pinfunction "K_2") (pintype "passive"))
      (node (ref "LD26") (pin "3") (pinfunction "3_3") (pintype "passive"))
      (node (ref "U3") (pin "14") (pinfunction "S5_14") (pintype "bidirectional"))
    )
    (net (code "46") (name "Net-(D43-K)") (class "Default")
      (node (ref "D43") (pin "2") (pinfunction "K_2") (pintype "passive"))
      (node (ref "LD25") (pin "3") (pinfunction "3_3") (pintype "passive"))
      (node (ref "U3") (pin "16") (pinfunction "S6_16") (pintype "bidirectional"))
    )
    (net (code "47") (name "Net-(U3-*RESET{slash}VL)") (class "Default")
      (node (ref "R40") (pin "1") (pinfunction "1_1") (pintype "passive"))
      (node (ref "U3") (pin "23") (pinfunction "*RESET/VL_23") (pintype "bidirectional"))
    )
    (net (code "48") (name "Net-(U3-SDO)") (class "Default")
      (node (ref "TP13") (pin "1") (pinfunction "1_1") (pintype "passive"))
      (node (ref "U3") (pin "22") (pinfunction "SDO_22") (pintype "output"))
    )
    (net (code "49") (name "Net-(U8-*RESET{slash}VL)") (class "Default")
      (node (ref "R39") (pin "1") (pinfunction "1_1") (pintype "passive"))
      (node (ref "U8") (pin "23") (pinfunction "*RESET/VL_23") (pintype "bidirectional"))
    )
    (net (code "50") (name "Net-(U9-*RESET{slash}VL)") (class "Default")
      (node (ref "R42") (pin "1") (pinfunction "1_1") (pintype "passive"))
      (node (ref "U9") (pin "23") (pinfunction "*RESET/VL_23") (pintype "bidirectional"))
    )
    (net (code "51") (name "Net-(U10-*RESET{slash}VL)") (class "Default")
      (node (ref "R44") (pin "1") (pinfunction "1_1") (pintype "passive"))
      (node (ref "U10") (pin "23") (pinfunction "*RESET/VL_23") (pintype "bidirectional"))
    )
  )
)
